# pl.net
KiCad netlist of a schematic drawn in EAGLE
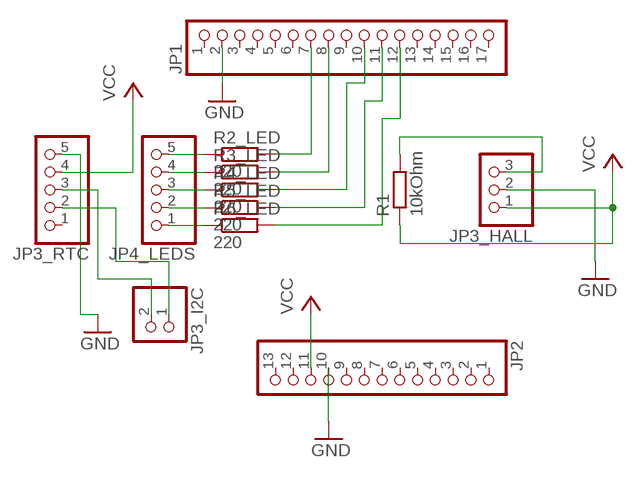
[diagram p0: schematic, sheet 1]

(export (version "E")
  (design (tool "Eeschema 10.0.6"))
  (components
    (comp (ref "JP1")
      (value "PINHD-1X17")
      (footprint "eagle-import:1X17")
      (libsource (lib "eagle-import") (part "PINHD-1X17"))
    )
    (comp (ref "JP2")
      (value "PINHD-1X13")
      (footprint "eagle-import:1X13")
      (libsource (lib "eagle-import") (part "PINHD-1X13"))
    )
    (comp (ref "JP3_HALL")
      (value "PINHD-1X3")
      (footprint "eagle-import:1X03")
      (libsource (lib "eagle-import") (part "PINHD-1X3"))
    )
    (comp (ref "JP3_I2C")
      (value "PINHD-1X2")
      (footprint "eagle-import:1X02")
      (libsource (lib "eagle-import") (part "PINHD-1X2"))
    )
    (comp (ref "JP3_RTC")
      (value "PINHD-1X5")
      (footprint "eagle-import:1X05")
      (libsource (lib "eagle-import") (part "PINHD-1X5"))
    )
    (comp (ref "JP4_LEDS")
      (value "PINHD-1X5")
      (footprint "eagle-import:1X05")
      (libsource (lib "eagle-import") (part "PINHD-1X5"))
    )
    (comp (ref "R1")
      (value "10kOhm")
      (footprint "eagle-import:R0805")
      (libsource (lib "eagle-import") (part "R-EU_R0805"))
    )
    (comp (ref "R2_LED")
      (value "220")
      (footprint "eagle-import:R0805")
      (libsource (lib "eagle-import") (part "resistor_R-EU_R0805"))
    )
    (comp (ref "R3_LED")
      (value "220")
      (footprint "eagle-import:R0805")
      (libsource (lib "eagle-import") (part "resistor_R-EU_R0805"))
    )
    (comp (ref "R4_LED")
      (value "220")
      (footprint "eagle-import:R0805")
      (libsource (lib "eagle-import") (part "resistor_R-EU_R0805"))
    )
    (comp (ref "R5_LED")
      (value "220")
      (footprint "eagle-import:R0805")
      (libsource (lib "eagle-import") (part "resistor_R-EU_R0805"))
    )
    (comp (ref "R6_LED")
      (value "220")
      (footprint "eagle-import:R0805")
      (libsource (lib "eagle-import") (part "resistor_R-EU_R0805"))
    )
  )
  (nets
    (net (code "1") (name "GND") (class "Default")
      (node (ref "JP1") (pin "2") (pinfunction "2_2") (pintype "passive"))
      (node (ref "JP2") (pin "10") (pinfunction "10_10") (pintype "passive"))
      (node (ref "JP3_HALL") (pin "2") (pinfunction "2_2") (pintype "passive"))
      (node (ref "JP3_RTC") (pin "5") (pinfunction "5_5") (pintype "passive"))
    )
    (net (code "2") (name "Net-(JP1-Pad7)") (class "Default")
      (node (ref "JP1") (pin "7") (pinfunction "7_7") (pintype "passive"))
      (node (ref "R2_LED") (pin "2") (pinfunction "2_2") (pintype "passive"))
    )
    (net (code "3") (name "Net-(JP1-Pad8)") (class "Default")
      (node (ref "JP1") (pin "8") (pinfunction "8_8") (pintype "passive"))
      (node (ref "R3_LED") (pin "2") (pinfunction "2_2") (pintype "passive"))
    )
    (net (code "4") (name "Net-(JP1-Pad10)") (class "Default")
      (node (ref "JP1") (pin "10") (pinfunction "10_10") (pintype "passive"))
      (node (ref "R4_LED") (pin "2") (pinfunction "2_2") (pintype "passive"))
    )
    (net (code "5") (name "Net-(JP1-Pad11)") (class "Default")
      (node (ref "JP1") (pin "11") (pinfunction "11_11") (pintype "passive"))
      (node (ref "R5_LED") (pin "2") (pinfunction "2_2") (pintype "passive"))
    )
    (net (code "6") (name "Net-(JP1-Pad12)") (class "Default")
      (node (ref "JP1") (pin "12") (pinfunction "12_12") (pintype "passive"))
      (node (ref "R6_LED") (pin "2") (pinfunction "2_2") (pintype "passive"))
    )
    (net (code "7") (name "Net-(JP3_HALL-Pad3)") (class "Default")
      (node (ref "JP3_HALL") (pin "3") (pinfunction "3_3") (pintype "passive"))
      (node (ref "R1") (pin "2") (pinfunction "2_2") (pintype "passive"))
    )
    (net (code "8") (name "Net-(JP3_I2C-Pad1)") (class "Default")
      (node (ref "JP3_I2C") (pin "1") (pinfunction "1_1") (pintype "passive"))
      (node (ref "JP3_RTC") (pin "2") (pinfunction "2_2") (pintype "passive"))
    )
    (net (code "9") (name "Net-(JP3_I2C-Pad2)") (class "Default")
      (node (ref "JP3_I2C") (pin "2") (pinfunction "2_2") (pintype "passive"))
      (node (ref "JP3_RTC") (pin "3") (pinfunction "3_3") (pintype "passive"))
    )
    (net (code "10") (name "Net-(JP4_LEDS-Pad1)") (class "Default")
      (node (ref "JP4_LEDS") (pin "1") (pinfunction "1_1") (pintype "passive"))
      (node (ref "R6_LED") (pin "1") (pinfunction "1_1") (pintype "passive"))
    )
    (net (code "11") (name "Net-(JP4_LEDS-Pad2)") (class "Default")
      (node (ref "JP4_LEDS") (pin "2") (pinfunction "2_2") (pintype "passive"))
      (node (ref "R5_LED") (pin "1") (pinfunction "1_1") (pintype "passive"))
    )
    (net (code "12") (name "Net-(JP4_LEDS-Pad3)") (class "Default")
      (node (ref "JP4_LEDS") (pin "3") (pinfunction "3_3") (pintype "passive"))
      (node (ref "R4_LED") (pin "1") (pinfunction "1_1") (pintype "passive"))
    )
    (net (code "13") (name "Net-(JP4_LEDS-Pad4)") (class "Default")
      (node (ref "JP4_LEDS") (pin "4") (pinfunction "4_4") (pintype "passive"))
      (node (ref "R3_LED") (pin "1") (pinfunction "1_1") (pintype "passive"))
    )
    (net (code "14") (name "Net-(JP4_LEDS-Pad5)") (class "Default")
      (node (ref "JP4_LEDS") (pin "5") (pinfunction "5_5") (pintype "passive"))
      (node (ref "R2_LED") (pin "1") (pinfunction "1_1") (pintype "passive"))
    )
    (net (code "15") (name "VCC") (class "Default")
      (node (ref "JP2") (pin "11") (pinfunction "11_11") (pintype "passive"))
      (node (ref "JP3_HALL") (pin "1") (pinfunction "1_1") (pintype "passive"))
      (node (ref "JP3_RTC") (pin "4") (pinfunction "4_4") (pintype "passive"))
      (node (ref "R1") (pin "1") (pinfunction "1_1") (pintype "passive"))
    )
    (net (code "16") (name "unconnected-(JP1-Pad1)") (class "Default")
      (node (ref "JP1") (pin "1") (pinfunction "1_1") (pintype "passive"))
    )
    (net (code "17") (name "unconnected-(JP1-Pad3)") (class "Default")
      (node (ref "JP1") (pin "3") (pinfunction "3_3") (pintype "passive"))
    )
    (net (code "18") (name "unconnected-(JP1-Pad4)") (class "Default")
      (node (ref "JP1") (pin "4") (pinfunction "4_4") (pintype "passive"))
    )
    (net (code "19") (name "unconnected-(JP1-Pad5)") (class "Default")
      (node (ref "JP1") (pin "5") (pinfunction "5_5") (pintype "passive"))
    )
    (net (code "20") (name "unconnected-(JP1-Pad6)") (class "Default")
      (node (ref "JP1") (pin "6") (pinfunction "6_6") (pintype "passive"))
    )
    (net (code "21") (name "unconnected-(JP1-Pad9)") (class "Default")
      (node (ref "JP1") (pin "9") (pinfunction "9_9") (pintype "passive"))
    )
    (net (code "22") (name "unconnected-(JP1-Pad13)") (class "Default")
      (node (ref "JP1") (pin "13") (pinfunction "13_13") (pintype "passive"))
    )
    (net (code "23") (name "unconnected-(JP1-Pad14)") (class "Default")
      (node (ref "JP1") (pin "14") (pinfunction "14_14") (pintype "passive"))
    )
    (net (code "24") (name "unconnected-(JP1-Pad15)") (class "Default")
      (node (ref "JP1") (pin "15") (pinfunction "15_15") (pintype "passive"))
    )
    (net (code "25") (name "unconnected-(JP1-Pad16)") (class "Default")
      (node (ref "JP1") (pin "16") (pinfunction "16_16") (pintype "passive"))
    )
    (net (code "26") (name "unconnected-(JP1-Pad17)") (class "Default")
      (node (ref "JP1") (pin "17") (pinfunction "17_17") (pintype "passive"))
    )
    (net (code "27") (name "unconnected-(JP2-Pad1)") (class "Default")
      (node (ref "JP2") (pin "1") (pinfunction "1_1") (pintype "passive"))
    )
    (net (code "28") (name "unconnected-(JP2-Pad2)") (class "Default")
      (node (ref "JP2") (pin "2") (pinfunction "2_2") (pintype "passive"))
    )
    (net (code "29") (name "unconnected-(JP2-Pad3)") (class "Default")
      (node (ref "JP2") (pin "3") (pinfunction "3_3") (pintype "passive"))
    )
    (net (code "30") (name "unconnected-(JP2-Pad4)") (class "Default")
      (node (ref "JP2") (pin "4") (pinfunction "4_4") (pintype "passive"))
    )
    (net (code "31") (name "unconnected-(JP2-Pad5)") (class "Default")
      (node (ref "JP2") (pin "5") (pinfunction "5_5") (pintype "passive"))
    )
    (net (code "32") (name "unconnected-(JP2-Pad6)") (class "Default")
      (node (ref "JP2") (pin "6") (pinfunction "6_6") (pintype "passive"))
    )
    (net (code "33") (name "unconnected-(JP2-Pad7)") (class "Default")
      (node (ref "JP2") (pin "7") (pinfunction "7_7") (pintype "passive"))
    )
    (net (code "34") (name "unconnected-(JP2-Pad8)") (class "Default")
      (node (ref "JP2") (pin "8") (pinfunction "8_8") (pintype "passive"))
    )
    (net (code "35") (name "unconnected-(JP2-Pad9)") (class "Default")
      (node (ref "JP2") (pin "9") (pinfunction "9_9") (pintype "passive"))
    )
    (net (code "36") (name "unconnected-(JP2-Pad12)") (class "Default")
      (node (ref "JP2") (pin "12") (pinfunction "12_12") (pintype "passive"))
    )
    (net (code "37") (name "unconnected-(JP2-Pad13)") (class "Default")
      (node (ref "JP2") (pin "13") (pinfunction "13_13") (pintype "passive"))
    )
    (net (code "38") (name "unconnected-(JP3_RTC-Pad1)") (class "Default")
      (node (ref "JP3_RTC") (pin "1") (pinfunction "1_1") (pintype "passive"))
    )
  )
)
